# SCT2XX0_INVERTING_STEP-DOWM.net
KiCad netlist of a schematic drawn in Altium Designer
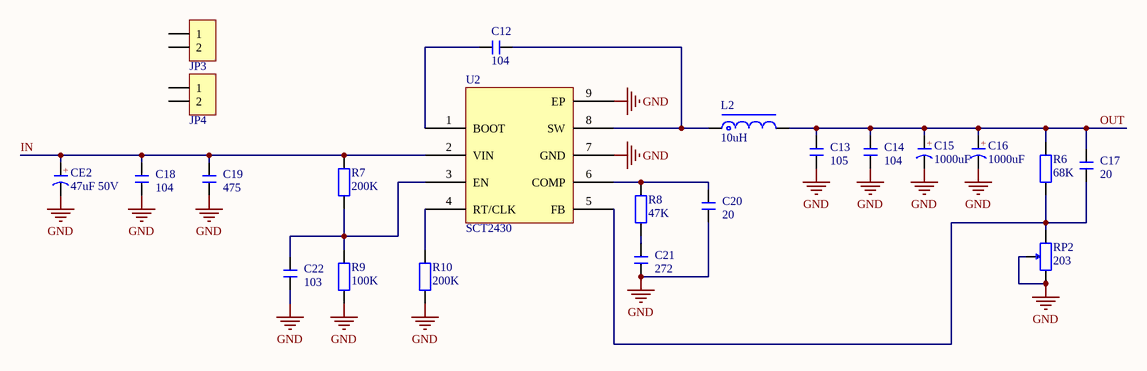
[diagram p0: SCT2XX0 INVERTING STEP-DOWM.SchDoc]

(export (version "E")
  (design (tool "Eeschema 10.0.6"))
  (components
    (comp (ref "C12")
      (value "104")
      (footprint "C 0805_L")
      (description "贴片电容")
      (libsource (lib "01 - 电容-电阻-电感") (part "C"))
    )
    (comp (ref "C13")
      (value "105")
      (footprint "C 0805_L")
      (description "贴片电容")
      (libsource (lib "01 - 电容-电阻-电感") (part "C"))
    )
    (comp (ref "C14")
      (value "104")
      (footprint "C 0805_L")
      (description "贴片电容")
      (libsource (lib "01 - 电容-电阻-电感") (part "C"))
    )
    (comp (ref "C15")
      (value "1000uF")
      (footprint "CAP 7.5*16*25")
      (description "直插电解电容")
      (libsource (lib "01 - 电容-电阻-电感") (part "CE"))
    )
    (comp (ref "C16")
      (value "1000uF")
      (footprint "CAP 5.0*12.5*20")
      (description "直插电解电容")
      (libsource (lib "01 - 电容-电阻-电感") (part "CE"))
    )
    (comp (ref "C17")
      (value "20")
      (footprint "C 0805_L")
      (description "贴片电容")
      (libsource (lib "01 - 电容-电阻-电感") (part "C"))
    )
    (comp (ref "C18")
      (value "104")
      (footprint "C 0805_L")
      (description "贴片电容")
      (libsource (lib "01 - 电容-电阻-电感") (part "C"))
    )
    (comp (ref "C19")
      (value "475")
      (footprint "C 0805_L")
      (description "贴片电容")
      (libsource (lib "01 - 电容-电阻-电感") (part "C"))
    )
    (comp (ref "C20")
      (value "20")
      (footprint "C 0805_L")
      (description "贴片电容")
      (libsource (lib "01 - 电容-电阻-电感") (part "C"))
    )
    (comp (ref "C21")
      (value "272")
      (footprint "C 0805_L")
      (description "贴片电容")
      (libsource (lib "01 - 电容-电阻-电感") (part "C"))
    )
    (comp (ref "C22")
      (value "103")
      (footprint "C 0805_L")
      (description "贴片电容")
      (libsource (lib "01 - 电容-电阻-电感") (part "C"))
    )
    (comp (ref "CE2")
      (value "47uF 50V")
      (footprint "CM C(5*5.4)")
      (description "贴片电解电容")
      (libsource (lib "01 - 电容-电阻-电感") (part "CE_SMD"))
    )
    (comp (ref "JP3")
      (value "HDR-1X2")
      (footprint "KF2510-LI-2P")
      (description "2P接插件")
      (libsource (lib "18 - 接插件-脚距2.54mm (100mil) ") (part "Header 2"))
    )
    (comp (ref "JP4")
      (value "HDR-1X2")
      (footprint "KF2510-LI-2P")
      (description "2P接插件")
      (libsource (lib "18 - 接插件-脚距2.54mm (100mil) ") (part "Header 2"))
    )
    (comp (ref "L2")
      (value "10uH")
      (footprint "CDRH127")
      (description "功率屏蔽电感")
      (libsource (lib "01 - 电容-电阻-电感") (part "L-CDRH"))
    )
    (comp (ref "R6")
      (value "68K")
      (footprint "R 0805_L")
      (description "贴片电阻")
      (libsource (lib "01 - 电容-电阻-电感") (part "R"))
    )
    (comp (ref "R7")
      (value "200K")
      (footprint "R 0805_L")
      (description "贴片电阻")
      (libsource (lib "01 - 电容-电阻-电感") (part "R"))
    )
    (comp (ref "R8")
      (value "47K")
      (footprint "R 0805_L")
      (description "贴片电阻")
      (libsource (lib "01 - 电容-电阻-电感") (part "R"))
    )
    (comp (ref "R9")
      (value "100K")
      (footprint "R 0805_L")
      (description "贴片电阻")
      (libsource (lib "01 - 电容-电阻-电感") (part "R"))
    )
    (comp (ref "R10")
      (value "200K")
      (footprint "R 0805_L")
      (description "贴片电阻")
      (libsource (lib "01 - 电容-电阻-电感") (part "R"))
    )
    (comp (ref "RP2")
      (value "203")
      (footprint "3296W")
      (description "单联电位器")
      (libsource (lib "01 - 电容-电阻-电感") (part "RP"))
    )
    (comp (ref "U2") (value "SCT2430") (footprint "ESOP8_N") (libsource (lib "10 - DC-DC") (part "SCT2430")))
  )
  (nets
    (net (code "1") (name "/IN") (class "Default")
      (node (ref "C18") (pin "2") (pinfunction "2_2") (pintype "passive"))
      (node (ref "C19") (pin "2") (pinfunction "2_2") (pintype "passive"))
      (node (ref "CE2") (pin "1") (pinfunction "A_1") (pintype "passive"))
      (node (ref "R7") (pin "2") (pinfunction "2_2") (pintype "passive"))
      (node (ref "U2") (pin "2") (pinfunction "VIN_2") (pintype "passive"))
    )
    (net (code "2") (name "/OUT") (class "Default")
      (node (ref "C13") (pin "2") (pinfunction "2_2") (pintype "passive"))
      (node (ref "C14") (pin "2") (pinfunction "2_2") (pintype "passive"))
      (node (ref "C15") (pin "1") (pinfunction "A_1") (pintype "passive"))
      (node (ref "C16") (pin "1") (pinfunction "A_1") (pintype "passive"))
      (node (ref "C17") (pin "2") (pinfunction "2_2") (pintype "passive"))
      (node (ref "L2") (pin "2") (pinfunction "2_2") (pintype "passive"))
      (node (ref "R6") (pin "2") (pinfunction "2_2") (pintype "passive"))
    )
    (net (code "3") (name "GND") (class "Default")
      (node (ref "C13") (pin "1") (pinfunction "1_1") (pintype "passive"))
      (node (ref "C14") (pin "1") (pinfunction "1_1") (pintype "passive"))
      (node (ref "C15") (pin "2") (pinfunction "K_2") (pintype "passive"))
      (node (ref "C16") (pin "2") (pinfunction "K_2") (pintype "passive"))
      (node (ref "C18") (pin "1") (pinfunction "1_1") (pintype "passive"))
      (node (ref "C19") (pin "1") (pinfunction "1_1") (pintype "passive"))
      (node (ref "C20") (pin "1") (pinfunction "1_1") (pintype "passive"))
      (node (ref "C21") (pin "1") (pinfunction "1_1") (pintype "passive"))
      (node (ref "C22") (pin "1") (pinfunction "1_1") (pintype "passive"))
      (node (ref "CE2") (pin "2") (pinfunction "K_2") (pintype "passive"))
      (node (ref "R10") (pin "1") (pinfunction "1_1") (pintype "passive"))
      (node (ref "R9") (pin "1") (pinfunction "1_1") (pintype "passive"))
      (node (ref "RP2") (pin "1") (pinfunction "1_1") (pintype "passive"))
      (node (ref "RP2") (pin "2") (pinfunction "2_2") (pintype "passive"))
      (node (ref "U2") (pin "7") (pinfunction "GND_7") (pintype "passive"))
      (node (ref "U2") (pin "9") (pinfunction "EP_9") (pintype "passive"))
    )
    (net (code "4") (name "Net-(C21-Pad2)") (class "Default")
      (node (ref "C21") (pin "2") (pinfunction "2_2") (pintype "passive"))
      (node (ref "R8") (pin "1") (pinfunction "1_1") (pintype "passive"))
    )
    (net (code "5") (name "Net-(U2-BOOT)") (class "Default")
      (node (ref "C12") (pin "1") (pinfunction "1_1") (pintype "passive"))
      (node (ref "U2") (pin "1") (pinfunction "BOOT_1") (pintype "passive"))
    )
    (net (code "6") (name "Net-(U2-COMP)") (class "Default")
      (node (ref "C20") (pin "2") (pinfunction "2_2") (pintype "passive"))
      (node (ref "R8") (pin "2") (pinfunction "2_2") (pintype "passive"))
      (node (ref "U2") (pin "6") (pinfunction "COMP_6") (pintype "passive"))
    )
    (net (code "7") (name "Net-(U2-EN)") (class "Default")
      (node (ref "C22") (pin "2") (pinfunction "2_2") (pintype "passive"))
      (node (ref "R7") (pin "1") (pinfunction "1_1") (pintype "passive"))
      (node (ref "R9") (pin "2") (pinfunction "2_2") (pintype "passive"))
      (node (ref "U2") (pin "3") (pinfunction "EN_3") (pintype "passive"))
    )
    (net (code "8") (name "Net-(U2-FB)") (class "Default")
      (node (ref "C17") (pin "1") (pinfunction "1_1") (pintype "passive"))
      (node (ref "R6") (pin "1") (pinfunction "1_1") (pintype "passive"))
      (node (ref "RP2") (pin "3") (pinfunction "3_3") (pintype "passive"))
      (node (ref "U2") (pin "5") (pinfunction "FB_5") (pintype "passive"))
    )
    (net (code "9") (name "Net-(U2-RT{slash}CLK)") (class "Default")
      (node (ref "R10") (pin "2") (pinfunction "2_2") (pintype "passive"))
      (node (ref "U2") (pin "4") (pinfunction "RT/CLK_4") (pintype "passive"))
    )
    (net (code "10") (name "Net-(U2-SW)") (class "Default")
      (node (ref "C12") (pin "2") (pinfunction "2_2") (pintype "passive"))
      (node (ref "L2") (pin "1") (pinfunction "1_1") (pintype "passive"))
      (node (ref "U2") (pin "8") (pinfunction "SW_8") (pintype "passive"))
    )
    (net (code "11") (name "unconnected-(JP3-Pad1)") (class "Default")
      (node (ref "JP3") (pin "1") (pinfunction "1_1") (pintype "passive"))
    )
    (net (code "12") (name "unconnected-(JP3-Pad2)") (class "Default")
      (node (ref "JP3") (pin "2") (pinfunction "2_2") (pintype "passive"))
    )
    (net (code "13") (name "unconnected-(JP4-Pad1)") (class "Default")
      (node (ref "JP4") (pin "1") (pinfunction "1_1") (pintype "passive"))
    )
    (net (code "14") (name "unconnected-(JP4-Pad2)") (class "Default")
      (node (ref "JP4") (pin "2") (pinfunction "2_2") (pintype "passive"))
    )
  )
)
